# Support.net
KiCad netlist of a schematic drawn in Altium Designer
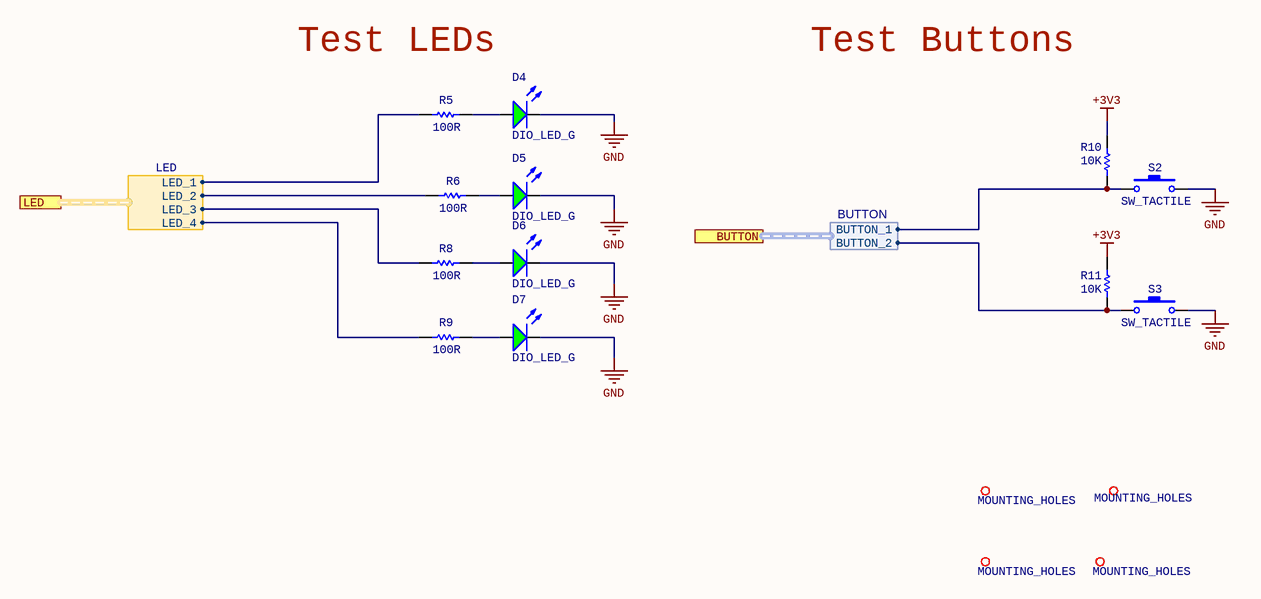
[diagram p0: Support.SchDoc]

(export (version "E")
  (design (tool "Eeschema 10.0.6"))
  (components
    (comp (ref "D4")
      (value "DIO_LED_G")
      (footprint "LED_0805_LINE")
      (description "LED GREEN DIFFUSED 0805 SMD")
      (fields (field (name "MANUFACTURER") "OSRAM") (field (name "MPN") "LG R971-KN-1"))
      (libsource (lib "UWRT_Schematic_Library_2020") (part "DIO_LED_G"))
    )
    (comp (ref "D5")
      (value "DIO_LED_G")
      (footprint "LED_0805_LINE")
      (description "LED GREEN DIFFUSED 0805 SMD")
      (fields (field (name "MANUFACTURER") "OSRAM") (field (name "MPN") "LG R971-KN-1"))
      (libsource (lib "UWRT_Schematic_Library_2020") (part "DIO_LED_G"))
    )
    (comp (ref "D6")
      (value "DIO_LED_G")
      (footprint "LED_0805_LINE")
      (description "LED GREEN DIFFUSED 0805 SMD")
      (fields (field (name "MANUFACTURER") "OSRAM") (field (name "MPN") "LG R971-KN-1"))
      (libsource (lib "UWRT_Schematic_Library_2020") (part "DIO_LED_G"))
    )
    (comp (ref "D7")
      (value "DIO_LED_G")
      (footprint "LED_0805_LINE")
      (description "LED GREEN DIFFUSED 0805 SMD")
      (fields (field (name "MANUFACTURER") "OSRAM") (field (name "MPN") "LG R971-KN-1"))
      (libsource (lib "UWRT_Schematic_Library_2020") (part "DIO_LED_G"))
    )
    (comp (ref "MH1")
      (value "MOUNTING_HOLES")
      (footprint "MOUNTING_HOLE")
      (description "6cm x 6cm")
      (libsource (lib "UWRT_Schematic_Library_2020") (part "MOUNTING_HOLES"))
    )
    (comp (ref "MH2")
      (value "MOUNTING_HOLES")
      (footprint "MOUNTING_HOLE")
      (description "6cm x 6cm")
      (libsource (lib "UWRT_Schematic_Library_2020") (part "MOUNTING_HOLES"))
    )
    (comp (ref "MH3")
      (value "MOUNTING_HOLES")
      (footprint "MOUNTING_HOLE")
      (description "6cm x 6cm")
      (libsource (lib "UWRT_Schematic_Library_2020") (part "MOUNTING_HOLES"))
    )
    (comp (ref "MH4")
      (value "MOUNTING_HOLES")
      (footprint "MOUNTING_HOLE")
      (description "6cm x 6cm")
      (libsource (lib "UWRT_Schematic_Library_2020") (part "MOUNTING_HOLES"))
    )
    (comp (ref "R5")
      (value "100R")
      (footprint "RESC0603(1608)_N")
      (description "RES SMD 100 OHM 1% 1/10W 0603")
      (fields (field (name "MANUFACTURER") "Yageo") (field (name "TOLERANCE") "1%"))
      (libsource (lib "UWRT_Schematic_Library_2020") (part "RES_100R_0603"))
    )
    (comp (ref "R6")
      (value "100R")
      (footprint "RESC0603(1608)_N")
      (description "RES SMD 100 OHM 1% 1/10W 0603")
      (fields (field (name "MANUFACTURER") "Yageo") (field (name "TOLERANCE") "1%"))
      (libsource (lib "UWRT_Schematic_Library_2020") (part "RES_100R_0603"))
    )
    (comp (ref "R8")
      (value "100R")
      (footprint "RESC0603(1608)_N")
      (description "RES SMD 100 OHM 1% 1/10W 0603")
      (fields (field (name "MANUFACTURER") "Yageo") (field (name "TOLERANCE") "1%"))
      (libsource (lib "UWRT_Schematic_Library_2020") (part "RES_100R_0603"))
    )
    (comp (ref "R9")
      (value "100R")
      (footprint "RESC0603(1608)_N")
      (description "RES SMD 100 OHM 1% 1/10W 0603")
      (fields (field (name "MANUFACTURER") "Yageo") (field (name "TOLERANCE") "1%"))
      (libsource (lib "UWRT_Schematic_Library_2020") (part "RES_100R_0603"))
    )
    (comp (ref "R10")
      (value "10K")
      (footprint "RESC0603(1608)_N")
      (description "RES SMD 10K OHM 5% 1/10W 0603")
      (fields (field (name "MANUFACTURER") "Yageo") (field (name "TOLERANCE") "5%"))
      (libsource (lib "UWRT_Schematic_Library_2020") (part "RES_10K_0603"))
    )
    (comp (ref "R11")
      (value "10K")
      (footprint "RESC0603(1608)_N")
      (description "RES SMD 10K OHM 5% 1/10W 0603")
      (fields (field (name "MANUFACTURER") "Yageo") (field (name "TOLERANCE") "5%"))
      (libsource (lib "UWRT_Schematic_Library_2020") (part "RES_10K_0603"))
    )
    (comp (ref "S2")
      (value "SW_TACTILE")
      (footprint "B3U-1100P")
      (description "Tactile Switch (Grey)")
      (fields (field (name "MPN") "B3U-1100P") (field (name "MANUFACTURER") "Omron Electronics Inc-EMC Div"))
      (libsource (lib "UWRT_Schematic_Library_2020") (part "SW_TACTILE"))
    )
    (comp (ref "S3")
      (value "SW_TACTILE")
      (footprint "B3U-1100P")
      (description "Tactile Switch (Grey)")
      (fields (field (name "MPN") "B3U-1100P") (field (name "MANUFACTURER") "Omron Electronics Inc-EMC Div"))
      (libsource (lib "UWRT_Schematic_Library_2020") (part "SW_TACTILE"))
    )
  )
  (nets
    (net (code "3") (name "+3V3") (class "Default")
      (node (ref "R10") (pin "1") (pinfunction "1_1") (pintype "passive"))
      (node (ref "R11") (pin "2") (pinfunction "2_2") (pintype "passive"))
    )
    (net (code "4") (name "/BUTTON_1") (class "Default")
      (node (ref "R10") (pin "2") (pinfunction "2_2") (pintype "passive"))
      (node (ref "S2") (pin "1") (pinfunction "1_1") (pintype "passive"))
    )
    (net (code "5") (name "/BUTTON_2") (class "Default")
      (node (ref "R11") (pin "1") (pinfunction "1_1") (pintype "passive"))
      (node (ref "S3") (pin "1") (pinfunction "1_1") (pintype "passive"))
    )
    (net (code "6") (name "/LED_1") (class "Default")
      (node (ref "R5") (pin "1") (pinfunction "1_1") (pintype "passive"))
    )
    (net (code "7") (name "/LED_2") (class "Default")
      (node (ref "R6") (pin "1") (pinfunction "1_1") (pintype "passive"))
    )
    (net (code "8") (name "/LED_3") (class "Default")
      (node (ref "R8") (pin "1") (pinfunction "1_1") (pintype "passive"))
    )
    (net (code "9") (name "/LED_4") (class "Default")
      (node (ref "R9") (pin "1") (pinfunction "1_1") (pintype "passive"))
    )
    (net (code "12") (name "GND") (class "Default")
      (node (ref "D4") (pin "2") (pinfunction "K_2") (pintype "passive"))
      (node (ref "D5") (pin "2") (pinfunction "K_2") (pintype "passive"))
      (node (ref "D6") (pin "2") (pinfunction "K_2") (pintype "passive"))
      (node (ref "D7") (pin "2") (pinfunction "K_2") (pintype "passive"))
      (node (ref "S2") (pin "2") (pinfunction "2_2") (pintype "passive"))
      (node (ref "S3") (pin "2") (pinfunction "2_2") (pintype "passive"))
    )
    (net (code "13") (name "Net-(D4-A)") (class "Default")
      (node (ref "D4") (pin "1") (pinfunction "A_1") (pintype "passive"))
      (node (ref "R5") (pin "2") (pinfunction "2_2") (pintype "passive"))
    )
    (net (code "14") (name "Net-(D5-A)") (class "Default")
      (node (ref "D5") (pin "1") (pinfunction "A_1") (pintype "passive"))
      (node (ref "R6") (pin "2") (pinfunction "2_2") (pintype "passive"))
    )
    (net (code "15") (name "Net-(D6-A)") (class "Default")
      (node (ref "D6") (pin "1") (pinfunction "A_1") (pintype "passive"))
      (node (ref "R8") (pin "2") (pinfunction "2_2") (pintype "passive"))
    )
    (net (code "16") (name "Net-(D7-A)") (class "Default")
      (node (ref "D7") (pin "1") (pinfunction "A_1") (pintype "passive"))
      (node (ref "R9") (pin "2") (pinfunction "2_2") (pintype "passive"))
    )
  )
)
